# 3_2.net
KiCad netlist of a schematic drawn in Altium Designer
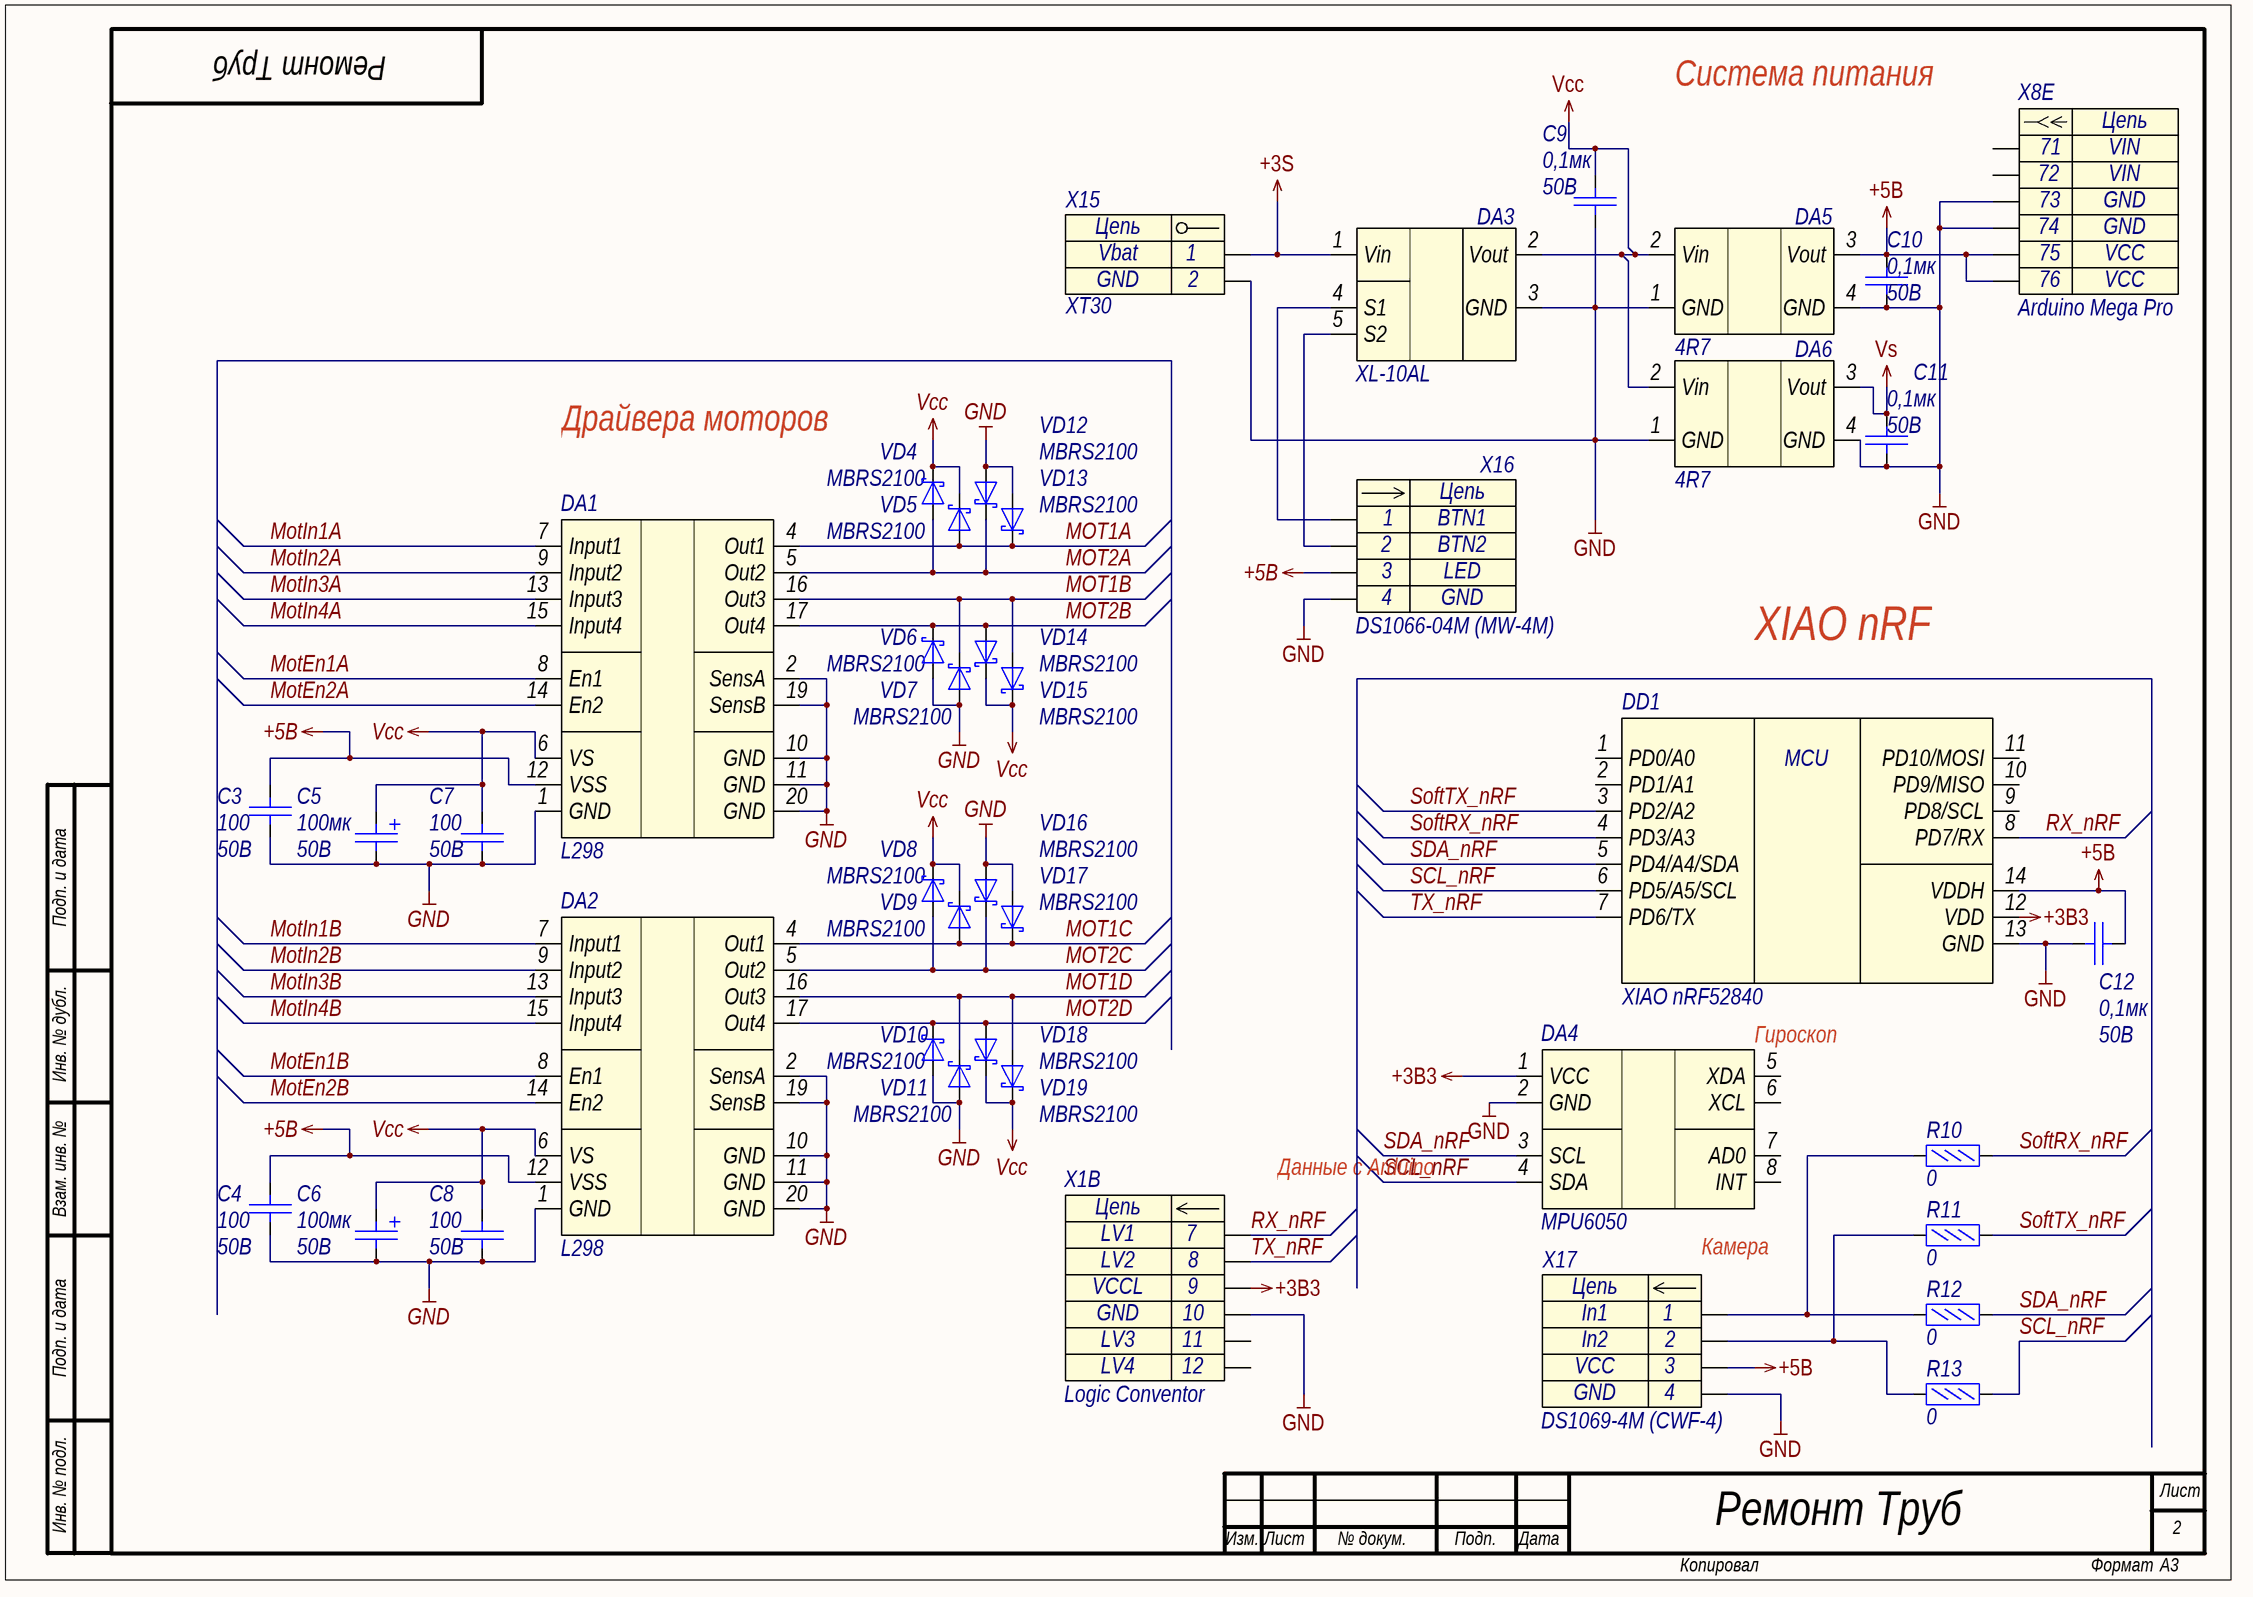
[diagram p0: Э3_2.SchDoc]

(export (version "E")
  (design (tool "Eeschema 10.0.6"))
  (components
    (comp (ref "C3")
      (value "100")
      (footprint "C0603")
      (description "Конденсатор кер. 100пФ 50В")
      (fields (field (name "MANUFACTURER") "Yageo") (field (name "VOLTAGE") "50В"))
      (libsource (lib "capacitors") (part "CC0603JRNPO9BN101"))
    )
    (comp (ref "C4")
      (value "100")
      (footprint "C0603")
      (description "Конденсатор кер. 100пФ 50В")
      (fields (field (name "MANUFACTURER") "Yageo") (field (name "VOLTAGE") "50В"))
      (libsource (lib "capacitors") (part "CC0603JRNPO9BN101"))
    )
    (comp (ref "C5")
      (value "100мк")
      (footprint "CAPALUM_8x11.5_V")
      (description "Конденсатор эл.лит. алюм. 100мкФ 50В")
      (fields (field (name "MANUFACTURER") "EPCOS") (field (name "VOLTAGE") "50В"))
      (libsource (lib "capacitors") (part "B41858C6107M"))
    )
    (comp (ref "C6")
      (value "100мк")
      (footprint "CAPALUM_8x11.5_V")
      (description "Конденсатор эл.лит. алюм. 100мкФ 50В")
      (fields (field (name "MANUFACTURER") "EPCOS") (field (name "VOLTAGE") "50В"))
      (libsource (lib "capacitors") (part "B41858C6107M"))
    )
    (comp (ref "C7")
      (value "100")
      (footprint "C0603")
      (description "Конденсатор кер. 100пФ 50В")
      (fields (field (name "MANUFACTURER") "Yageo") (field (name "VOLTAGE") "50В"))
      (libsource (lib "capacitors") (part "CC0603JRNPO9BN101"))
    )
    (comp (ref "C8")
      (value "100")
      (footprint "C0603")
      (description "Конденсатор кер. 100пФ 50В")
      (fields (field (name "MANUFACTURER") "Yageo") (field (name "VOLTAGE") "50В"))
      (libsource (lib "capacitors") (part "CC0603JRNPO9BN101"))
    )
    (comp (ref "C9")
      (value "0,1мк")
      (footprint "C0603")
      (description "Конденсатор кер. 0,1мкФ 50В X7R")
      (fields (field (name "MANUFACTURER") "Murata") (field (name "VOLTAGE") "50В"))
      (libsource (lib "capacitors") (part "GRM188R71H104KA93D"))
    )
    (comp (ref "C10")
      (value "0,1мк")
      (footprint "C0603")
      (description "Конденсатор кер. 0,1мкФ 50В X7R")
      (fields (field (name "MANUFACTURER") "Murata") (field (name "VOLTAGE") "50В"))
      (libsource (lib "capacitors") (part "GRM188R71H104KA93D"))
    )
    (comp (ref "C11")
      (value "0,1мк")
      (footprint "C0603")
      (description "Конденсатор кер. 0,1мкФ 50В X7R")
      (fields (field (name "MANUFACTURER") "Murata") (field (name "VOLTAGE") "50В"))
      (libsource (lib "capacitors") (part "GRM188R71H104KA93D"))
    )
    (comp (ref "C12")
      (value "0,1мк")
      (footprint "C0603")
      (description "Конденсатор кер. 0,1мкФ 50В X7R")
      (fields (field (name "MANUFACTURER") "Murata") (field (name "VOLTAGE") "50В"))
      (libsource (lib "capacitors") (part "GRM188R71H104KA93D"))
    )
    (comp (ref "DA1")
      (value "L298")
      (footprint "L298P")
      (description "Драйвер двигателя")
      (fields (field (name "MANUFACTURER") "China") (field (name "NAME") "L298"))
      (libsource (lib "ics") (part "L298"))
    )
    (comp (ref "DA2")
      (value "L298")
      (footprint "L298P")
      (description "Драйвер двигателя")
      (fields (field (name "MANUFACTURER") "China") (field (name "NAME") "L298"))
      (libsource (lib "ics") (part "L298"))
    )
    (comp (ref "DA3")
      (value "XL-10AL")
      (footprint "XL-10AL")
      (fields (field (name "MANUFACTURER") "China") (field (name "NAME") "XL-10AL"))
      (libsource (lib "ics") (part "XL-10AL"))
    )
    (comp (ref "DA4")
      (value "MPU6050")
      (footprint "MPU6050")
      (description "Гироскоп и акселерометр")
      (fields (field (name "MANUFACTURER") "China") (field (name "NAME") "MPU6050"))
      (libsource (lib "ics") (part "MPU6050"))
    )
    (comp (ref "DA5")
      (value "4R7")
      (footprint "mini360")
      (description "Линейный стабилизатор напряжения 14.4В -> 5В")
      (fields (field (name "MANUFACTURER") "China") (field (name "NAME") "4R7"))
      (libsource (lib "ics") (part "4R7"))
    )
    (comp (ref "DA6")
      (value "4R7")
      (footprint "mini360")
      (description "Линейный стабилизатор напряжения 14.4В -> 5В")
      (fields (field (name "MANUFACTURER") "China") (field (name "NAME") "4R7"))
      (libsource (lib "ics") (part "4R7"))
    )
    (comp (ref "DD1")
      (value "XIAO nRF52840")
      (footprint "Seeed Studio XIAO nRF52840")
      (description "Микроконтроллер nRF52840")
      (libsource (lib "MCU") (part "XIAO nRF52840"))
    )
    (comp (ref "R10")
      (value "0")
      (footprint "R0603")
      (description "Перемычка 0603")
      (libsource (lib "resistors") (part "Перемычка 0603"))
    )
    (comp (ref "R11")
      (value "0")
      (footprint "R0603")
      (description "Перемычка 0603")
      (libsource (lib "resistors") (part "Перемычка 0603"))
    )
    (comp (ref "R12")
      (value "0")
      (footprint "R0603")
      (description "Перемычка 0603")
      (libsource (lib "resistors") (part "Перемычка 0603"))
    )
    (comp (ref "R13")
      (value "0")
      (footprint "R0603")
      (description "Перемычка 0603")
      (libsource (lib "resistors") (part "Перемычка 0603"))
    )
    (comp (ref "VD4")
      (value "MBRS2100")
      (footprint "DO-214AA")
      (description "Диод Шоттки 100В 2А")
      (fields (field (name "NAME") "MBRS2100"))
      (libsource (lib "diodes") (part "MBRS2100"))
    )
    (comp (ref "VD5")
      (value "MBRS2100")
      (footprint "DO-214AA")
      (description "Диод Шоттки 100В 2А")
      (fields (field (name "NAME") "MBRS2100"))
      (libsource (lib "diodes") (part "MBRS2100"))
    )
    (comp (ref "VD6")
      (value "MBRS2100")
      (footprint "DO-214AA")
      (description "Диод Шоттки 100В 2А")
      (fields (field (name "NAME") "MBRS2100"))
      (libsource (lib "diodes") (part "MBRS2100"))
    )
    (comp (ref "VD7")
      (value "MBRS2100")
      (footprint "DO-214AA")
      (description "Диод Шоттки 100В 2А")
      (fields (field (name "NAME") "MBRS2100"))
      (libsource (lib "diodes") (part "MBRS2100"))
    )
    (comp (ref "VD8")
      (value "MBRS2100")
      (footprint "DO-214AA")
      (description "Диод Шоттки 100В 2А")
      (fields (field (name "NAME") "MBRS2100"))
      (libsource (lib "diodes") (part "MBRS2100"))
    )
    (comp (ref "VD9")
      (value "MBRS2100")
      (footprint "DO-214AA")
      (description "Диод Шоттки 100В 2А")
      (fields (field (name "NAME") "MBRS2100"))
      (libsource (lib "diodes") (part "MBRS2100"))
    )
    (comp (ref "VD10")
      (value "MBRS2100")
      (footprint "DO-214AA")
      (description "Диод Шоттки 100В 2А")
      (fields (field (name "NAME") "MBRS2100"))
      (libsource (lib "diodes") (part "MBRS2100"))
    )
    (comp (ref "VD11")
      (value "MBRS2100")
      (footprint "DO-214AA")
      (description "Диод Шоттки 100В 2А")
      (fields (field (name "NAME") "MBRS2100"))
      (libsource (lib "diodes") (part "MBRS2100"))
    )
    (comp (ref "VD12")
      (value "MBRS2100")
      (footprint "DO-214AA")
      (description "Диод Шоттки 100В 2А")
      (fields (field (name "NAME") "MBRS2100"))
      (libsource (lib "diodes") (part "MBRS2100"))
    )
    (comp (ref "VD13")
      (value "MBRS2100")
      (footprint "DO-214AA")
      (description "Диод Шоттки 100В 2А")
      (fields (field (name "NAME") "MBRS2100"))
      (libsource (lib "diodes") (part "MBRS2100"))
    )
    (comp (ref "VD14")
      (value "MBRS2100")
      (footprint "DO-214AA")
      (description "Диод Шоттки 100В 2А")
      (fields (field (name "NAME") "MBRS2100"))
      (libsource (lib "diodes") (part "MBRS2100"))
    )
    (comp (ref "VD15")
      (value "MBRS2100")
      (footprint "DO-214AA")
      (description "Диод Шоттки 100В 2А")
      (fields (field (name "NAME") "MBRS2100"))
      (libsource (lib "diodes") (part "MBRS2100"))
    )
    (comp (ref "VD16")
      (value "MBRS2100")
      (footprint "DO-214AA")
      (description "Диод Шоттки 100В 2А")
      (fields (field (name "NAME") "MBRS2100"))
      (libsource (lib "diodes") (part "MBRS2100"))
    )
    (comp (ref "VD17")
      (value "MBRS2100")
      (footprint "DO-214AA")
      (description "Диод Шоттки 100В 2А")
      (fields (field (name "NAME") "MBRS2100"))
      (libsource (lib "diodes") (part "MBRS2100"))
    )
    (comp (ref "VD18")
      (value "MBRS2100")
      (footprint "DO-214AA")
      (description "Диод Шоттки 100В 2А")
      (fields (field (name "NAME") "MBRS2100"))
      (libsource (lib "diodes") (part "MBRS2100"))
    )
    (comp (ref "VD19")
      (value "MBRS2100")
      (footprint "DO-214AA")
      (description "Диод Шоттки 100В 2А")
      (fields (field (name "NAME") "MBRS2100"))
      (libsource (lib "diodes") (part "MBRS2100"))
    )
    (comp (ref "X1")
      (value "Logic Conventor")
      (footprint "LOGIC CONVENTOR")
      (description "Преобразователь уровней")
      (fields (field (name "NAME") "Logic Conventor"))
      (libsource (lib "headers") (part "Logic Conventor"))
    )
    (comp (ref "X8")
      (value "Arduino Mega Pro")
      (footprint "Arduino Mega Pro Mini")
      (description "Arduino Mega Pro Mini")
      (fields (field (name "NAME") "Arduino Mega Pro"))
      (libsource (lib "headers") (part "Arduino Mega Pro Mini"))
    )
    (comp (ref "X15")
      (value "XT30")
      (footprint "XT30 - duplicate")
      (fields (field (name "NAME") "XT30"))
      (libsource (lib "headers") (part "XT30"))
    )
    (comp (ref "X16")
      (value "DS1066-04M (MW-4M)")
      (footprint "MW-4M")
      (description "Разъем - 4 конт. прямая вилка на плату")
      (fields (field (name "NAME") "DS1066-04M (MW-4M)"))
      (libsource (lib "headers") (part "MW-4M"))
    )
    (comp (ref "X17")
      (value "DS1069-4M (CWF-4)")
      (footprint "CWF-4")
      (description "Разъем - 4 конт. прямая вилка на плату")
      (fields (field (name "NAME") "DS1069-4M (CWF-4)"))
      (libsource (lib "headers") (part "CWF-4"))
    )
  )
  (nets
    (net (code "1") (name "+3B3") (class "Default")
      (node (ref "DA4") (pin "1") (pinfunction "VCC_1") (pintype "passive"))
      (node (ref "DD1") (pin "12") (pinfunction "VDD_12") (pintype "passive"))
      (node (ref "X1") (pin "9") (pinfunction "9_9") (pintype "passive"))
    )
    (net (code "2") (name "+3S") (class "Default")
      (node (ref "DA3") (pin "1") (pinfunction "Vin_1") (pintype "passive"))
      (node (ref "X15") (pin "1") (pinfunction "1_1") (pintype "passive"))
    )
    (net (code "3") (name "+5B") (class "Default")
      (node (ref "C10") (pin "2") (pinfunction "2_2") (pintype "passive"))
      (node (ref "C12") (pin "2") (pinfunction "2_2") (pintype "passive"))
      (node (ref "C3") (pin "1") (pinfunction "1_1") (pintype "passive"))
      (node (ref "C4") (pin "1") (pinfunction "1_1") (pintype "passive"))
      (node (ref "DA1") (pin "12") (pinfunction "VSS_12") (pintype "passive"))
      (node (ref "DA2") (pin "12") (pinfunction "VSS_12") (pintype "passive"))
      (node (ref "DA5") (pin "3") (pinfunction "Vout_3") (pintype "passive"))
      (node (ref "DD1") (pin "14") (pinfunction "VDDH_14") (pintype "passive"))
      (node (ref "X16") (pin "3") (pinfunction "3_3") (pintype "passive"))
      (node (ref "X17") (pin "3") (pinfunction "3_3") (pintype "passive"))
      (node (ref "X8") (pin "75") (pinfunction "75_75") (pintype "passive"))
      (node (ref "X8") (pin "76") (pinfunction "76_76") (pintype "passive"))
    )
    (net (code "5") (name "/MOT1A") (class "Default")
      (node (ref "DA1") (pin "4") (pinfunction "Out1_4") (pintype "passive"))
      (node (ref "VD13") (pin "1") (pinfunction "K_1") (pintype "passive"))
      (node (ref "VD5") (pin "2") (pinfunction "A_2") (pintype "passive"))
    )
    (net (code "6") (name "/MOT1B") (class "Default")
      (node (ref "DA1") (pin "16") (pinfunction "Out3_16") (pintype "passive"))
      (node (ref "VD15") (pin "2") (pinfunction "A_2") (pintype "passive"))
      (node (ref "VD7") (pin "1") (pinfunction "K_1") (pintype "passive"))
    )
    (net (code "7") (name "/MOT1C") (class "Default")
      (node (ref "DA2") (pin "4") (pinfunction "Out1_4") (pintype "passive"))
      (node (ref "VD17") (pin "1") (pinfunction "K_1") (pintype "passive"))
      (node (ref "VD9") (pin "2") (pinfunction "A_2") (pintype "passive"))
    )
    (net (code "8") (name "/MOT1D") (class "Default")
      (node (ref "DA2") (pin "16") (pinfunction "Out3_16") (pintype "passive"))
      (node (ref "VD11") (pin "1") (pinfunction "K_1") (pintype "passive"))
      (node (ref "VD19") (pin "2") (pinfunction "A_2") (pintype "passive"))
    )
    (net (code "9") (name "/MOT2A") (class "Default")
      (node (ref "DA1") (pin "5") (pinfunction "Out2_5") (pintype "passive"))
      (node (ref "VD12") (pin "1") (pinfunction "K_1") (pintype "passive"))
      (node (ref "VD4") (pin "2") (pinfunction "A_2") (pintype "passive"))
    )
    (net (code "10") (name "/MOT2B") (class "Default")
      (node (ref "DA1") (pin "17") (pinfunction "Out4_17") (pintype "passive"))
      (node (ref "VD14") (pin "2") (pinfunction "A_2") (pintype "passive"))
      (node (ref "VD6") (pin "1") (pinfunction "K_1") (pintype "passive"))
    )
    (net (code "11") (name "/MOT2C") (class "Default")
      (node (ref "DA2") (pin "5") (pinfunction "Out2_5") (pintype "passive"))
      (node (ref "VD16") (pin "1") (pinfunction "K_1") (pintype "passive"))
      (node (ref "VD8") (pin "2") (pinfunction "A_2") (pintype "passive"))
    )
    (net (code "12") (name "/MOT2D") (class "Default")
      (node (ref "DA2") (pin "17") (pinfunction "Out4_17") (pintype "passive"))
      (node (ref "VD10") (pin "1") (pinfunction "K_1") (pintype "passive"))
      (node (ref "VD18") (pin "2") (pinfunction "A_2") (pintype "passive"))
    )
    (net (code "13") (name "/MotEn1A") (class "Default")
      (node (ref "DA1") (pin "8") (pinfunction "En1_8") (pintype "passive"))
    )
    (net (code "14") (name "/MotEn1B") (class "Default")
      (node (ref "DA2") (pin "8") (pinfunction "En1_8") (pintype "passive"))
    )
    (net (code "15") (name "/MotEn2A") (class "Default")
      (node (ref "DA1") (pin "14") (pinfunction "En2_14") (pintype "passive"))
    )
    (net (code "16") (name "/MotEn2B") (class "Default")
      (node (ref "DA2") (pin "14") (pinfunction "En2_14") (pintype "passive"))
    )
    (net (code "17") (name "/MotIn1A") (class "Default")
      (node (ref "DA1") (pin "7") (pinfunction "Input1_7") (pintype "passive"))
    )
    (net (code "18") (name "/MotIn1B") (class "Default")
      (node (ref "DA2") (pin "7") (pinfunction "Input1_7") (pintype "passive"))
    )
    (net (code "19") (name "/MotIn2A") (class "Default")
      (node (ref "DA1") (pin "9") (pinfunction "Input2_9") (pintype "passive"))
    )
    (net (code "20") (name "/MotIn2B") (class "Default")
      (node (ref "DA2") (pin "9") (pinfunction "Input2_9") (pintype "passive"))
    )
    (net (code "21") (name "/MotIn3A") (class "Default")
      (node (ref "DA1") (pin "13") (pinfunction "Input3_13") (pintype "passive"))
    )
    (net (code "22") (name "/MotIn3B") (class "Default")
      (node (ref "DA2") (pin "13") (pinfunction "Input3_13") (pintype "passive"))
    )
    (net (code "23") (name "/MotIn4A") (class "Default")
      (node (ref "DA1") (pin "15") (pinfunction "Input4_15") (pintype "passive"))
    )
    (net (code "24") (name "/MotIn4B") (class "Default")
      (node (ref "DA2") (pin "15") (pinfunction "Input4_15") (pintype "passive"))
    )
    (net (code "25") (name "/RX_nRF") (class "Default")
      (node (ref "DD1") (pin "8") (pinfunction "PD7/RX_8") (pintype "passive"))
      (node (ref "X1") (pin "7") (pinfunction "7_7") (pintype "passive"))
    )
    (net (code "26") (name "/SCL_nRF") (class "Default")
      (node (ref "DA4") (pin "4") (pinfunction "SDA_4") (pintype "passive"))
      (node (ref "DD1") (pin "6") (pinfunction "PD5/A5/SCL_6") (pintype "passive"))
      (node (ref "R13") (pin "2") (pinfunction "2_2") (pintype "passive"))
    )
    (net (code "27") (name "/SDA_nRF") (class "Default")
      (node (ref "DA4") (pin "3") (pinfunction "SCL_3") (pintype "passive"))
      (node (ref "DD1") (pin "5") (pinfunction "PD4/A4/SDA_5") (pintype "passive"))
      (node (ref "R12") (pin "2") (pinfunction "2_2") (pintype "passive"))
    )
    (net (code "28") (name "/SoftRX_nRF") (class "Default")
      (node (ref "DD1") (pin "4") (pinfunction "PD3/A3_4") (pintype "passive"))
      (node (ref "R10") (pin "2") (pinfunction "2_2") (pintype "passive"))
    )
    (net (code "29") (name "/SoftTX_nRF") (class "Default")
      (node (ref "DD1") (pin "3") (pinfunction "PD2/A2_3") (pintype "passive"))
      (node (ref "R11") (pin "2") (pinfunction "2_2") (pintype "passive"))
    )
    (net (code "30") (name "/TX_nRF") (class "Default")
      (node (ref "DD1") (pin "7") (pinfunction "PD6/TX_7") (pintype "passive"))
      (node (ref "X1") (pin "8") (pinfunction "8_8") (pintype "passive"))
    )
    (net (code "31") (name "GND") (class "Default")
      (node (ref "C10") (pin "1") (pinfunction "1_1") (pintype "passive"))
      (node (ref "C11") (pin "1") (pinfunction "1_1") (pintype "passive"))
      (node (ref "C12") (pin "1") (pinfunction "1_1") (pintype "passive"))
      (node (ref "C3") (pin "2") (pinfunction "2_2") (pintype "passive"))
      (node (ref "C4") (pin "2") (pinfunction "2_2") (pintype "passive"))
      (node (ref "C5") (pin "2") (pinfunction "2_2") (pintype "passive"))
      (node (ref "C6") (pin "2") (pinfunction "2_2") (pintype "passive"))
      (node (ref "C7") (pin "1") (pinfunction "1_1") (pintype "passive"))
      (node (ref "C8") (pin "1") (pinfunction "1_1") (pintype "passive"))
      (node (ref "C9") (pin "1") (pinfunction "1_1") (pintype "passive"))
      (node (ref "DA1") (pin "1") (pinfunction "GND_1") (pintype "passive"))
      (node (ref "DA1") (pin "10") (pinfunction "GND_10") (pintype "passive"))
      (node (ref "DA1") (pin "11") (pinfunction "GND_11") (pintype "passive"))
      (node (ref "DA1") (pin "19") (pinfunction "SensB_19") (pintype "passive"))
      (node (ref "DA1") (pin "2") (pinfunction "SensA_2") (pintype "passive"))
      (node (ref "DA1") (pin "20") (pinfunction "GND_20") (pintype "passive"))
      (node (ref "DA2") (pin "1") (pinfunction "GND_1") (pintype "passive"))
      (node (ref "DA2") (pin "10") (pinfunction "GND_10") (pintype "passive"))
      (node (ref "DA2") (pin "11") (pinfunction "GND_11") (pintype "passive"))
      (node (ref "DA2") (pin "19") (pinfunction "SensB_19") (pintype "passive"))
      (node (ref "DA2") (pin "2") (pinfunction "SensA_2") (pintype "passive"))
      (node (ref "DA2") (pin "20") (pinfunction "GND_20") (pintype "passive"))
      (node (ref "DA3") (pin "3") (pinfunction "GND_3") (pintype "passive"))
      (node (ref "DA4") (pin "2") (pinfunction "GND_2") (pintype "passive"))
      (node (ref "DA5") (pin "1") (pinfunction "GND_1") (pintype "passive"))
      (node (ref "DA5") (pin "4") (pinfunction "GND_4") (pintype "passive"))
      (node (ref "DA6") (pin "1") (pinfunction "GND_1") (pintype "passive"))
      (node (ref "DA6") (pin "4") (pinfunction "GND_4") (pintype "passive"))
      (node (ref "DD1") (pin "13") (pinfunction "GND_13") (pintype "passive"))
      (node (ref "VD10") (pin "2") (pinfunction "A_2") (pintype "passive"))
      (node (ref "VD11") (pin "2") (pinfunction "A_2") (pintype "passive"))
      (node (ref "VD12") (pin "2") (pinfunction "A_2") (pintype "passive"))
      (node (ref "VD13") (pin "2") (pinfunction "A_2") (pintype "passive"))
      (node (ref "VD16") (pin "2") (pinfunction "A_2") (pintype "passive"))
      (node (ref "VD17") (pin "2") (pinfunction "A_2") (pintype "passive"))
      (node (ref "VD6") (pin "2") (pinfunction "A_2") (pintype "passive"))
      (node (ref "VD7") (pin "2") (pinfunction "A_2") (pintype "passive"))
      (node (ref "X1") (pin "10") (pinfunction "10_10") (pintype "passive"))
      (node (ref "X15") (pin "2") (pinfunction "2_2") (pintype "passive"))
      (node (ref "X16") (pin "4") (pinfunction "4_4") (pintype "passive"))
      (node (ref "X17") (pin "4") (pinfunction "4_4") (pintype "passive"))
      (node (ref "X8") (pin "73") (pinfunction "73_73") (pintype "passive"))
      (node (ref "X8") (pin "74") (pinfunction "74_74") (pintype "passive"))
    )
    (net (code "32") (name "Net-(DA3-S1)") (class "Default")
      (node (ref "DA3") (pin "4") (pinfunction "S1_4") (pintype "passive"))
      (node (ref "X16") (pin "1") (pinfunction "1_1") (pintype "passive"))
    )
    (net (code "33") (name "Net-(DA3-S2)") (class "Default")
      (node (ref "DA3") (pin "5") (pinfunction "S2_5") (pintype "passive"))
      (node (ref "X16") (pin "2") (pinfunction "2_2") (pintype "passive"))
    )
    (net (code "34") (name "Net-(R10-Pad1)") (class "Default")
      (node (ref "R10") (pin "1") (pinfunction "1_1") (pintype "passive"))
      (node (ref "R12") (pin "1") (pinfunction "1_1") (pintype "passive"))
      (node (ref "X17") (pin "1") (pinfunction "1_1") (pintype "passive"))
    )
    (net (code "35") (name "Net-(R11-Pad1)") (class "Default")
      (node (ref "R11") (pin "1") (pinfunction "1_1") (pintype "passive"))
      (node (ref "R13") (pin "1") (pinfunction "1_1") (pintype "passive"))
      (node (ref "X17") (pin "2") (pinfunction "2_2") (pintype "passive"))
    )
    (net (code "36") (name "Vcc") (class "Default")
      (node (ref "C5") (pin "1") (pinfunction "1_1") (pintype "passive"))
      (node (ref "C6") (pin "1") (pinfunction "1_1") (pintype "passive"))
      (node (ref "C7") (pin "2") (pinfunction "2_2") (pintype "passive"))
      (node (ref "C8") (pin "2") (pinfunction "2_2") (pintype "passive"))
      (node (ref "C9") (pin "2") (pinfunction "2_2") (pintype "passive"))
      (node (ref "DA1") (pin "6") (pinfunction "VS_6") (pintype "passive"))
      (node (ref "DA2") (pin "6") (pinfunction "VS_6") (pintype "passive"))
      (node (ref "DA3") (pin "2") (pinfunction "Vout_2") (pintype "passive"))
      (node (ref "DA5") (pin "2") (pinfunction "Vin_2") (pintype "passive"))
      (node (ref "DA6") (pin "2") (pinfunction "Vin_2") (pintype "passive"))
      (node (ref "VD14") (pin "1") (pinfunction "K_1") (pintype "passive"))
      (node (ref "VD15") (pin "1") (pinfunction "K_1") (pintype "passive"))
      (node (ref "VD18") (pin "1") (pinfunction "K_1") (pintype "passive"))
      (node (ref "VD19") (pin "1") (pinfunction "K_1") (pintype "passive"))
      (node (ref "VD4") (pin "1") (pinfunction "K_1") (pintype "passive"))
      (node (ref "VD5") (pin "1") (pinfunction "K_1") (pintype "passive"))
      (node (ref "VD8") (pin "1") (pinfunction "K_1") (pintype "passive"))
      (node (ref "VD9") (pin "1") (pinfunction "K_1") (pintype "passive"))
    )
    (net (code "37") (name "Vs") (class "Default")
      (node (ref "C11") (pin "2") (pinfunction "2_2") (pintype "passive"))
      (node (ref "DA6") (pin "3") (pinfunction "Vout_3") (pintype "passive"))
    )
    (net (code "38") (name "unconnected-(DA4-AD0-Pad7)") (class "Default")
      (node (ref "DA4") (pin "7") (pinfunction "AD0_7") (pintype "passive"))
    )
    (net (code "39") (name "unconnected-(DA4-INT-Pad8)") (class "Default")
      (node (ref "DA4") (pin "8") (pinfunction "INT_8") (pintype "passive"))
    )
    (net (code "40") (name "unconnected-(DA4-XCL-Pad6)") (class "Default")
      (node (ref "DA4") (pin "6") (pinfunction "XCL_6") (pintype "passive"))
    )
    (net (code "41") (name "unconnected-(DA4-XDA-Pad5)") (class "Default")
      (node (ref "DA4") (pin "5") (pinfunction "XDA_5") (pintype "passive"))
    )
    (net (code "42") (name "unconnected-(DD1-PD0{slash}A0-Pad1)") (class "Default")
      (node (ref "DD1") (pin "1") (pinfunction "PD0/A0_1") (pintype "passive"))
    )
    (net (code "43") (name "unconnected-(DD1-PD1{slash}A1-Pad2)") (class "Default")
      (node (ref "DD1") (pin "2") (pinfunction "PD1/A1_2") (pintype "passive"))
    )
    (net (code "44") (name "unconnected-(DD1-PD8{slash}SCL-Pad9)") (class "Default")
      (node (ref "DD1") (pin "9") (pinfunction "PD8/SCL_9") (pintype "passive"))
    )
    (net (code "45") (name "unconnected-(DD1-PD9{slash}MISO-Pad10)") (class "Default")
      (node (ref "DD1") (pin "10") (pinfunction "PD9/MISO_10") (pintype "passive"))
    )
    (net (code "46") (name "unconnected-(DD1-PD10{slash}MOSI-Pad11)") (class "Default")
      (node (ref "DD1") (pin "11") (pinfunction "PD10/MOSI_11") (pintype "passive"))
    )
    (net (code "47") (name "unconnected-(X1-Pad11)") (class "Default")
      (node (ref "X1") (pin "11") (pinfunction "11_11") (pintype "passive"))
    )
    (net (code "48") (name "unconnected-(X1-Pad12)") (class "Default")
      (node (ref "X1") (pin "12") (pinfunction "12_12") (pintype "passive"))
    )
    (net (code "49") (name "unconnected-(X8-Pad71)") (class "Default")
      (node (ref "X8") (pin "71") (pinfunction "71_71") (pintype "passive"))
    )
    (net (code "50") (name "unconnected-(X8-Pad72)") (class "Default")
      (node (ref "X8") (pin "72") (pinfunction "72_72") (pintype "passive"))
    )
  )
)
